# RFOUT_DaughterBoard.net
KiCad netlist of a schematic drawn in Altium Designer
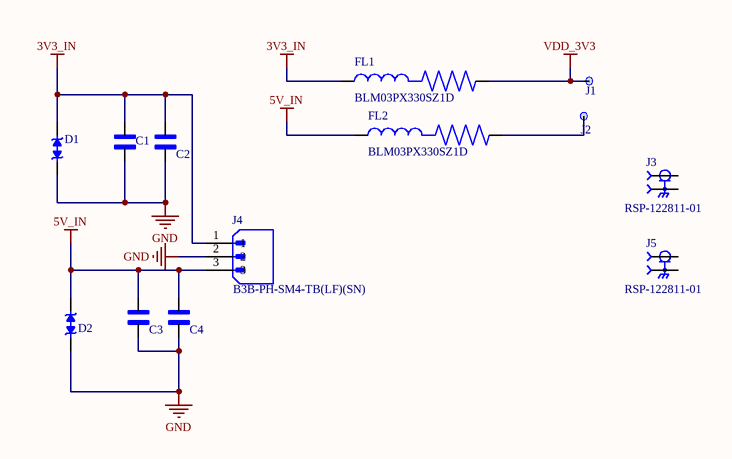
[diagram p0: RFOUT DaughterBoard.SchDoc]

(export (version "E")
  (design (tool "Eeschema 10.0.6"))
  (components
    (comp (ref "C1")
      (value "CC0603KRX5R9BB105")
      (footprint "CAPC1608X90")
      (description "1 ÂµF Â±10% 50V Ceramic Capacitor X5R 0603 (1608 Metric)")
      (fields (field (name "MF") "Yageo"))
      (libsource (lib "CC0603KRX5R9BB105") (part "CC0603KRX5R9BB105"))
    )
    (comp (ref "C2")
      (value "CC0603KRX5R9BB105")
      (footprint "CAPC1608X90")
      (description "1 ÂµF Â±10% 50V Ceramic Capacitor X5R 0603 (1608 Metric)")
      (fields (field (name "MF") "Yageo"))
      (libsource (lib "CC0603KRX5R9BB105") (part "CC0603KRX5R9BB105"))
    )
    (comp (ref "C3")
      (value "CC0603KRX5R9BB105")
      (footprint "CAPC1608X90")
      (description "1 ÂµF Â±10% 50V Ceramic Capacitor X5R 0603 (1608 Metric)")
      (fields (field (name "MF") "Yageo"))
      (libsource (lib "CC0603KRX5R9BB105") (part "CC0603KRX5R9BB105"))
    )
    (comp (ref "C4")
      (value "CC0603KRX5R9BB105")
      (footprint "CAPC1608X90")
      (description "1 ÂµF Â±10% 50V Ceramic Capacitor X5R 0603 (1608 Metric)")
      (fields (field (name "MF") "Yageo"))
      (libsource (lib "CC0603KRX5R9BB105") (part "CC0603KRX5R9BB105"))
    )
    (comp (ref "D1")
      (value "TESDL5V0B12P1Q0_M7G")
      (footprint "DFN61X31X34-2N")
      (fields (field (name "MF") "{'manufacturer': u'Taiwan Semiconductor'}"))
      (libsource (lib "TESDL5V0B12P1Q0_M7G") (part "TESDL5V0B12P1Q0_M7G"))
    )
    (comp (ref "D2")
      (value "TESDL5V0B12P1Q0_M7G")
      (footprint "DFN61X31X34-2N")
      (fields (field (name "MF") "{'manufacturer': u'Taiwan Semiconductor'}"))
      (libsource (lib "TESDL5V0B12P1Q0_M7G") (part "TESDL5V0B12P1Q0_M7G"))
    )
    (comp (ref "FL1")
      (value "BLM03PX330SZ1D")
      (footprint "BEADC0603X33N")
      (description "33 Ohms @ 100 MHz 1 Power Line Ferrite Bead 0201 (0603 Metric) 1.5A 55mOhm")
      (fields (field (name "MF") "Murata"))
      (libsource (lib "BLM03PX330SZ1D") (part "BLM03PX330SZ1D"))
    )
    (comp (ref "FL2")
      (value "BLM03PX330SZ1D")
      (footprint "BEADC0603X33N")
      (description "33 Ohms @ 100 MHz 1 Power Line Ferrite Bead 0201 (0603 Metric) 1.5A 55mOhm")
      (fields (field (name "MF") "Murata"))
      (libsource (lib "BLM03PX330SZ1D") (part "BLM03PX330SZ1D"))
    )
    (comp (ref "J1")
      (value "Testpoint, Surface, 1.0mm")
      (footprint "TP_1mm_UN1Q")
      (description "Testpoint 1.0mm")
      (fields (field (name "PART NUMBER") "TP 1mm"))
      (libsource (lib "robo_cam") (part "CMP-001-000153-12"))
    )
    (comp (ref "J2")
      (value "Testpoint, Surface, 1.0mm")
      (footprint "TP_1mm_UN1Q")
      (description "Testpoint 1.0mm")
      (fields (field (name "PART NUMBER") "TP 1mm"))
      (libsource (lib "robo_cam") (part "CMP-001-000153-12"))
    )
    (comp (ref "J3")
      (value "RSP-122811-01")
      (footprint "SAMTEC_RSP-122811-01")
      (fields (field (name "MF") "{'manufacturer': u'Samtec Inc.'}"))
      (libsource (lib "RSP-122811-01") (part "RSP-122811-01"))
    )
    (comp (ref "J4")
      (value "B3B-PH-SM4-TB(LF)(SN)")
      (footprint "JST_B3B-PH-SM4-TB(LF)(SN)")
      (description "Connector Header Surface Mount 3 position 0.079 (2.00mm)")
      (fields (field (name "MF") "JST Sales"))
      (libsource (lib "B3B-PH-SM4-TB_LF__SN_") (part "B3B-PH-SM4-TB(LF)(SN)"))
    )
    (comp (ref "J5")
      (value "RSP-122811-01")
      (footprint "SAMTEC_RSP-122811-01")
      (fields (field (name "MF") "{'manufacturer': u'Samtec Inc.'}"))
      (libsource (lib "RSP-122811-01") (part "RSP-122811-01"))
    )
  )
  (nets
    (net (code "1") (name "3V3_IN") (class "Default")
      (node (ref "C1") (pin "1") (pinfunction "1_1") (pintype "passive"))
      (node (ref "C2") (pin "1") (pinfunction "1_1") (pintype "passive"))
      (node (ref "D1") (pin "2") (pinfunction "2_2") (pintype "passive"))
      (node (ref "FL1") (pin "1") (pinfunction "1_1") (pintype "passive"))
      (node (ref "J4") (pin "1") (pinfunction "1_1") (pintype "passive"))
    )
    (net (code "2") (name "5V_IN") (class "Default")
      (node (ref "C3") (pin "1") (pinfunction "1_1") (pintype "passive"))
      (node (ref "C4") (pin "1") (pinfunction "1_1") (pintype "passive"))
      (node (ref "D2") (pin "2") (pinfunction "2_2") (pintype "passive"))
      (node (ref "FL2") (pin "1") (pinfunction "1_1") (pintype "passive"))
      (node (ref "J4") (pin "3") (pinfunction "3_3") (pintype "passive"))
    )
    (net (code "3") (name "GND") (class "Default")
      (node (ref "C1") (pin "2") (pinfunction "2_2") (pintype "passive"))
      (node (ref "C2") (pin "2") (pinfunction "2_2") (pintype "passive"))
      (node (ref "C3") (pin "2") (pinfunction "2_2") (pintype "passive"))
      (node (ref "C4") (pin "2") (pinfunction "2_2") (pintype "passive"))
      (node (ref "D1") (pin "1") (pinfunction "1_1") (pintype "passive"))
      (node (ref "D2") (pin "1") (pinfunction "1_1") (pintype "passive"))
      (node (ref "J4") (pin "2") (pinfunction "2_2") (pintype "passive"))
    )
    (net (code "4") (name "Net-(J2-TP)") (class "Default")
      (node (ref "FL2") (pin "2") (pinfunction "2_2") (pintype "passive"))
      (node (ref "J2") (pin "1") (pinfunction "TP_1") (pintype "passive"))
    )
    (net (code "5") (name "Net-(J3-GND-PadG1)") (class "Default")
      (node (ref "J3") (pin "G1") (pinfunction "GND_G1") (pintype "passive"))
      (node (ref "J3") (pin "G2") (pinfunction "GND_G2") (pintype "passive"))
    )
    (net (code "6") (name "Net-(J5-GND-PadG1)") (class "Default")
      (node (ref "J5") (pin "G1") (pinfunction "GND_G1") (pintype "passive"))
      (node (ref "J5") (pin "G2") (pinfunction "GND_G2") (pintype "passive"))
    )
    (net (code "7") (name "VDD_3V3") (class "Default")
      (node (ref "FL1") (pin "2") (pinfunction "2_2") (pintype "passive"))
      (node (ref "J1") (pin "1") (pinfunction "TP_1") (pintype "passive"))
    )
    (net (code "8") (name "unconnected-(J3-Pad1)") (class "Default")
      (node (ref "J3") (pin "1") (pinfunction "1_1") (pintype "passive"))
    )
    (net (code "9") (name "unconnected-(J5-Pad1)") (class "Default")
      (node (ref "J5") (pin "1") (pinfunction "1_1") (pintype "passive"))
    )
  )
)
